# design.net
KiCad netlist of a schematic drawn in EasyEDA Pro
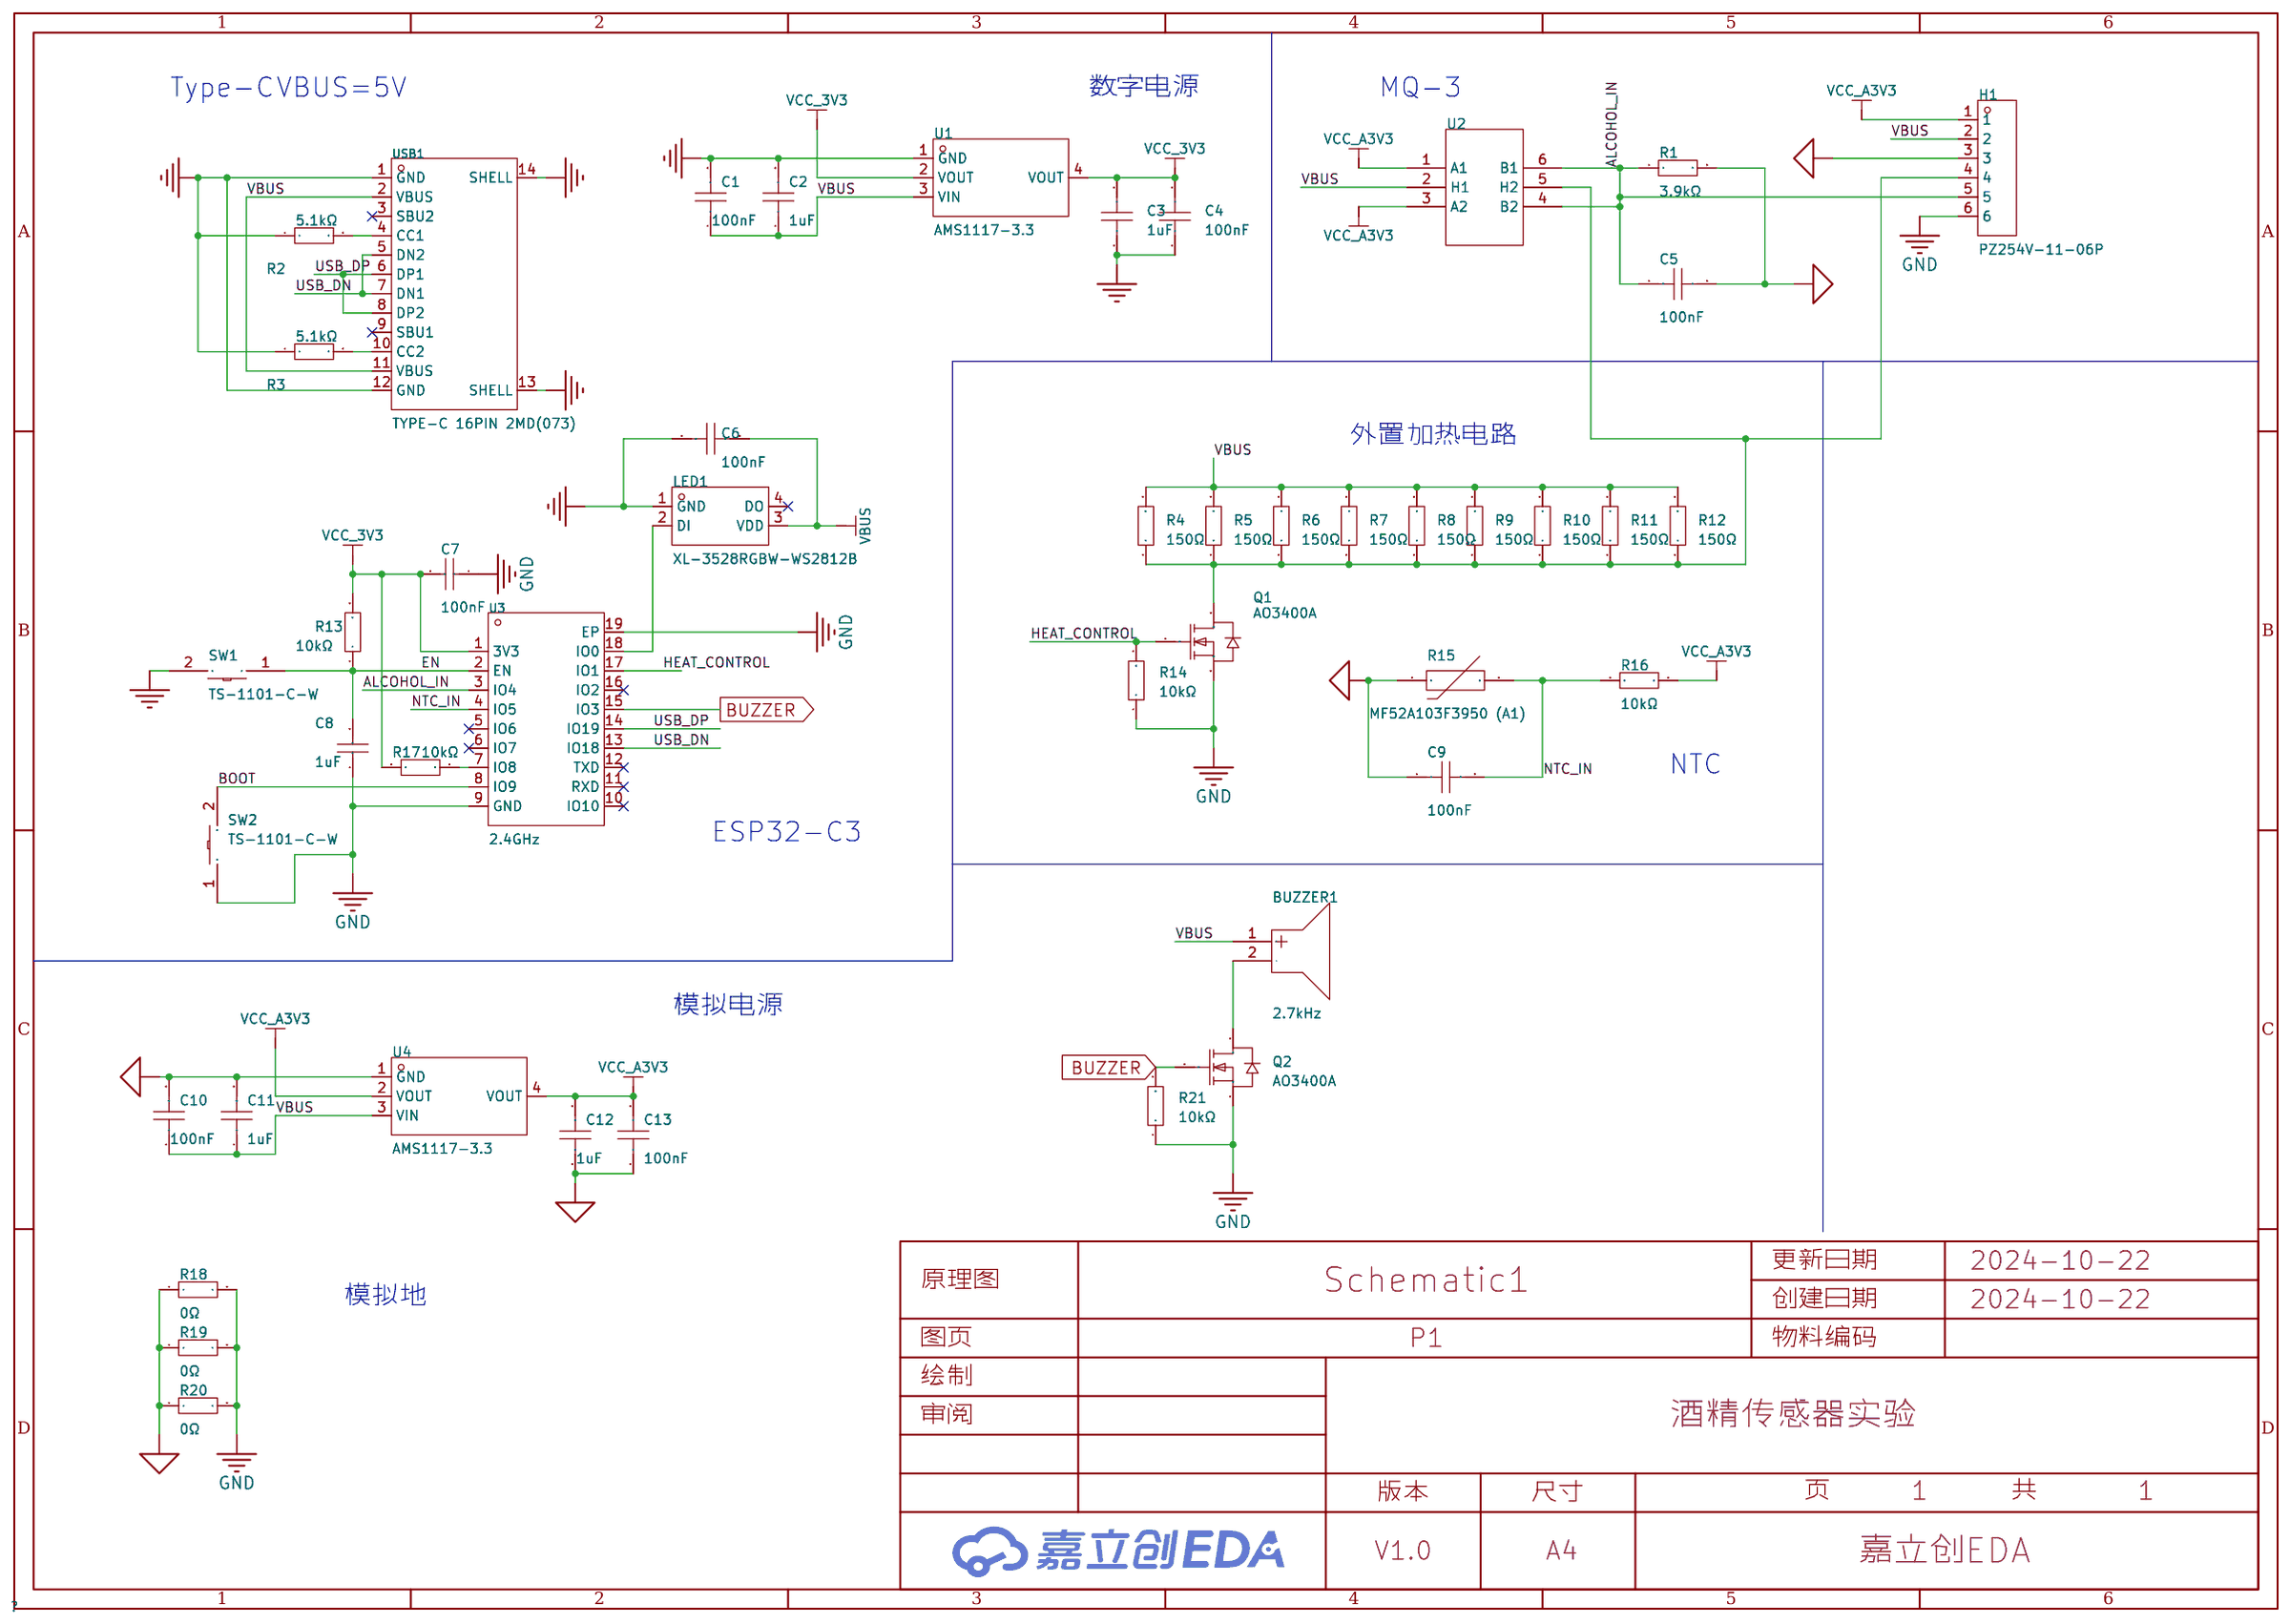
[diagram p0: schematic sheet]

(export (version "E")
  (design (tool "Eeschema 10.0.6"))
  (components
    (comp (ref "BUZZER1")
      (value "2.7kHz")
      (footprint "easyedapro:BUZ-SMD_L9.6-W9.6-LS10.0-R")
      (description "驱动方式:有源(内含驱动线路);频率:2.7kHz;声压(SPL):80dB@5V,10cm;")
      (fields
        (field (name "Manufacturer Part") "YS-SBZ9650DYB05")
        (field (name "Manufacturer") "Fengming(锋鸣电子)")
      )
      (libsource (lib "easyedapro") (part "YS-SBZ9650DYB05_C409830"))
    )
    (comp (ref "C1")
      (value "100nF")
      (footprint "easyedapro:C0603")
      (description "容值:100nF;精度:±10%;额定电压:50V;材质(温度系数):X7R;")
      (fields
        (field (name "Manufacturer Part") "CC0603KRX7R9BB104")
        (field (name "Manufacturer") "YAGEO(国巨)")
      )
      (libsource (lib "easyedapro") (part "CC0603KRX7R9BB104"))
    )
    (comp (ref "C2")
      (value "1uF")
      (footprint "easyedapro:C0603")
      (description "容值:1uF;精度:±10%;额定电压:50V;材质(温度系数):X5R;")
      (fields
        (field (name "Manufacturer Part") "CL10A105KB8NNNC")
        (field (name "Manufacturer") "SAMSUNG(三星)")
      )
      (libsource (lib "easyedapro") (part "CL10A105KB8NNNC"))
    )
    (comp (ref "C3")
      (value "1uF")
      (footprint "easyedapro:C0603")
      (description "容值:1uF;精度:±10%;额定电压:50V;材质(温度系数):X5R;")
      (fields
        (field (name "Manufacturer Part") "CL10A105KB8NNNC")
        (field (name "Manufacturer") "SAMSUNG(三星)")
      )
      (libsource (lib "easyedapro") (part "CL10A105KB8NNNC"))
    )
    (comp (ref "C4")
      (value "100nF")
      (footprint "easyedapro:C0603")
      (description "容值:100nF;精度:±10%;额定电压:50V;材质(温度系数):X7R;")
      (fields
        (field (name "Manufacturer Part") "CC0603KRX7R9BB104")
        (field (name "Manufacturer") "YAGEO(国巨)")
      )
      (libsource (lib "easyedapro") (part "CC0603KRX7R9BB104"))
    )
    (comp (ref "C5")
      (value "100nF")
      (footprint "easyedapro:C0603")
      (description "容值:100nF;精度:±10%;额定电压:50V;材质(温度系数):X7R;")
      (fields
        (field (name "Manufacturer Part") "CGA0603X7R104K500JT")
        (field (name "Manufacturer") "HRE(芯声)")
      )
      (libsource (lib "easyedapro") (part "cga0603x7r104k500jt"))
    )
    (comp (ref "C6")
      (value "100nF")
      (footprint "easyedapro:C0603")
      (description "容值:100nF;精度:±10%;额定电压:50V;材质(温度系数):X7R;")
      (fields
        (field (name "Manufacturer Part") "CC0603KRX7R9BB104")
        (field (name "Manufacturer") "YAGEO(国巨)")
      )
      (libsource (lib "easyedapro") (part "CC0603KRX7R9BB104"))
    )
    (comp (ref "C7")
      (value "100nF")
      (footprint "easyedapro:C0603")
      (description "容值:1uF;精度:±10%;额定电压:25V;温度系数:X5R;")
      (fields
        (field (name "Manufacturer Part") "CC0603KRX7R9BB104")
        (field (name "Manufacturer") "YAGEO(国巨)")
      )
      (libsource (lib "easyedapro") (part "CL10A105KA8NNNC"))
    )
    (comp (ref "C8")
      (value "1uF")
      (footprint "easyedapro:C0603")
      (description "容值:1uF;精度:±10%;额定电压:25V;温度系数:X5R;")
      (fields
        (field (name "Manufacturer Part") "CL10A105KA8NNNC")
        (field (name "Manufacturer") "SAMSUNG(三星)")
      )
      (libsource (lib "easyedapro") (part "CL10A105KA8NNNC"))
    )
    (comp (ref "C9")
      (value "100nF")
      (footprint "easyedapro:C0603")
      (description "容值:100nF;精度:±10%;额定电压:50V;材质(温度系数):X7R;")
      (fields
        (field (name "Manufacturer Part") "CGA0603X7R104K500JT")
        (field (name "Manufacturer") "HRE(芯声)")
      )
      (libsource (lib "easyedapro") (part "cga0603x7r104k500jt"))
    )
    (comp (ref "C10")
      (value "100nF")
      (footprint "easyedapro:C0603")
      (description "容值:100nF;精度:±10%;额定电压:50V;材质(温度系数):X7R;")
      (fields
        (field (name "Manufacturer Part") "CC0603KRX7R9BB104")
        (field (name "Manufacturer") "YAGEO(国巨)")
      )
      (libsource (lib "easyedapro") (part "CC0603KRX7R9BB104"))
    )
    (comp (ref "C11")
      (value "1uF")
      (footprint "easyedapro:C0603")
      (description "容值:1uF;精度:±10%;额定电压:50V;材质(温度系数):X5R;")
      (fields
        (field (name "Manufacturer Part") "CL10A105KB8NNNC")
        (field (name "Manufacturer") "SAMSUNG(三星)")
      )
      (libsource (lib "easyedapro") (part "CL10A105KB8NNNC"))
    )
    (comp (ref "C12")
      (value "1uF")
      (footprint "easyedapro:C0603")
      (description "容值:1uF;精度:±10%;额定电压:50V;材质(温度系数):X5R;")
      (fields
        (field (name "Manufacturer Part") "CL10A105KB8NNNC")
        (field (name "Manufacturer") "SAMSUNG(三星)")
      )
      (libsource (lib "easyedapro") (part "CL10A105KB8NNNC"))
    )
    (comp (ref "C13")
      (value "100nF")
      (footprint "easyedapro:C0603")
      (description "容值:100nF;精度:±10%;额定电压:50V;材质(温度系数):X7R;")
      (fields
        (field (name "Manufacturer Part") "CC0603KRX7R9BB104")
        (field (name "Manufacturer") "YAGEO(国巨)")
      )
      (libsource (lib "easyedapro") (part "CC0603KRX7R9BB104"))
    )
    (comp (ref "H1")
      (value "PZ254V-11-06P")
      (footprint "easyedapro:HDR-TH_6P-P2.54-V-M")
      (fields (field (name "Manufacturer") "XFCN(兴飞)"))
      (libsource (lib "easyedapro") (part "PZ254V-11-06P"))
    )
    (comp (ref "LED1")
      (value "XL-3528RGBW-WS2812B")
      (footprint "easyedapro:LED-SMD_4P-L3.5-W2.8-BR-1")
      (description "3528 七彩幻彩雾状 ws2812B 内置驱动IC")
      (fields (field (name "Manufacturer") "XINGLIGHT(成兴光)"))
      (libsource (lib "easyedapro") (part "XL-3528RGBW-WS2812B"))
    )
    (comp (ref "Q1")
      (value "AO3400A")
      (footprint "easyedapro:SOT-23-3_L2.9-W1.3-P1.90-LS2.4-BR")
      (fields (field (name "Manufacturer") "AOS"))
      (libsource (lib "easyedapro") (part "AO3400A"))
    )
    (comp (ref "Q2")
      (value "AO3400A")
      (footprint "easyedapro:SOT-23-3_L2.9-W1.3-P1.90-LS2.4-BR")
      (fields (field (name "Manufacturer") "AOS"))
      (libsource (lib "easyedapro") (part "AO3400A"))
    )
    (comp (ref "R1")
      (value "3.9kΩ")
      (footprint "easyedapro:R0603")
      (description "电阻类型:厚膜电阻;阻值:3.9kΩ;精度:±1%;功率:100mW;最大工作电压:75V;温度系数:±100ppm/°C;")
      (fields
        (field (name "Manufacturer Part") "0603WAF3901T5E")
        (field (name "Manufacturer") "UNI-ROYAL(厚声)")
      )
      (libsource (lib "easyedapro") (part "0603WAF3901T5E"))
    )
    (comp (ref "R2")
      (value "5.1kΩ")
      (fields
        (field (name "Manufacturer Part") "0603WAF5101T5E")
        (field (name "Manufacturer") "UNI-ROYAL(厚声)")
      )
      (libsource (lib "easyedapro") (part "电阻"))
    )
    (comp (ref "R3")
      (value "5.1kΩ")
      (fields
        (field (name "Manufacturer Part") "0603WAF5101T5E")
        (field (name "Manufacturer") "UNI-ROYAL(厚声)")
      )
      (libsource (lib "easyedapro") (part "电阻"))
    )
    (comp (ref "R4")
      (value "150Ω")
      (footprint "easyedapro:R0603")
      (description "电阻类型:厚膜电阻;阻值:150Ω;精度:±1%;功率:100mW;温度系数:±100ppm/°C;")
      (fields
        (field (name "Manufacturer Part") "0603WAF1500T5E")
        (field (name "Manufacturer") "UNI-ROYAL(厚声)")
      )
      (libsource (lib "easyedapro") (part "0603WAF1500T5E"))
    )
    (comp (ref "R5")
      (value "150Ω")
      (footprint "easyedapro:R0603")
      (description "电阻类型:厚膜电阻;阻值:150Ω;精度:±1%;功率:100mW;温度系数:±100ppm/°C;")
      (fields
        (field (name "Manufacturer Part") "0603WAF1500T5E")
        (field (name "Manufacturer") "UNI-ROYAL(厚声)")
      )
      (libsource (lib "easyedapro") (part "0603WAF1500T5E"))
    )
    (comp (ref "R6")
      (value "150Ω")
      (footprint "easyedapro:R0603")
      (description "电阻类型:厚膜电阻;阻值:150Ω;精度:±1%;功率:100mW;温度系数:±100ppm/°C;")
      (fields
        (field (name "Manufacturer Part") "0603WAF1500T5E")
        (field (name "Manufacturer") "UNI-ROYAL(厚声)")
      )
      (libsource (lib "easyedapro") (part "0603WAF1500T5E"))
    )
    (comp (ref "R7")
      (value "150Ω")
      (footprint "easyedapro:R0603")
      (description "电阻类型:厚膜电阻;阻值:150Ω;精度:±1%;功率:100mW;温度系数:±100ppm/°C;")
      (fields
        (field (name "Manufacturer Part") "0603WAF1500T5E")
        (field (name "Manufacturer") "UNI-ROYAL(厚声)")
      )
      (libsource (lib "easyedapro") (part "0603WAF1500T5E"))
    )
    (comp (ref "R8")
      (value "150Ω")
      (footprint "easyedapro:R0603")
      (description "电阻类型:厚膜电阻;阻值:150Ω;精度:±1%;功率:100mW;温度系数:±100ppm/°C;")
      (fields
        (field (name "Manufacturer Part") "0603WAF1500T5E")
        (field (name "Manufacturer") "UNI-ROYAL(厚声)")
      )
      (libsource (lib "easyedapro") (part "0603WAF1500T5E"))
    )
    (comp (ref "R9")
      (value "150Ω")
      (footprint "easyedapro:R0603")
      (description "电阻类型:厚膜电阻;阻值:150Ω;精度:±1%;功率:100mW;温度系数:±100ppm/°C;")
      (fields
        (field (name "Manufacturer Part") "0603WAF1500T5E")
        (field (name "Manufacturer") "UNI-ROYAL(厚声)")
      )
      (libsource (lib "easyedapro") (part "0603WAF1500T5E"))
    )
    (comp (ref "R10")
      (value "150Ω")
      (footprint "easyedapro:R0603")
      (description "电阻类型:厚膜电阻;阻值:150Ω;精度:±1%;功率:100mW;温度系数:±100ppm/°C;")
      (fields
        (field (name "Manufacturer Part") "0603WAF1500T5E")
        (field (name "Manufacturer") "UNI-ROYAL(厚声)")
      )
      (libsource (lib "easyedapro") (part "0603WAF1500T5E"))
    )
    (comp (ref "R11")
      (value "150Ω")
      (footprint "easyedapro:R0603")
      (description "电阻类型:厚膜电阻;阻值:150Ω;精度:±1%;功率:100mW;温度系数:±100ppm/°C;")
      (fields
        (field (name "Manufacturer Part") "0603WAF1500T5E")
        (field (name "Manufacturer") "UNI-ROYAL(厚声)")
      )
      (libsource (lib "easyedapro") (part "0603WAF1500T5E"))
    )
    (comp (ref "R12")
      (value "150Ω")
      (footprint "easyedapro:R0603")
      (description "电阻类型:厚膜电阻;阻值:150Ω;精度:±1%;功率:100mW;温度系数:±100ppm/°C;")
      (fields
        (field (name "Manufacturer Part") "0603WAF1500T5E")
        (field (name "Manufacturer") "UNI-ROYAL(厚声)")
      )
      (libsource (lib "easyedapro") (part "0603WAF1500T5E"))
    )
    (comp (ref "R13")
      (value "10kΩ")
      (fields
        (field (name "Manufacturer Part") "0603WAF1002T5E")
        (field (name "Manufacturer") "UNI-ROYAL(厚声)")
      )
      (libsource (lib "easyedapro") (part "电阻"))
    )
    (comp (ref "R14")
      (value "10kΩ")
      (fields
        (field (name "Manufacturer Part") "0603WAF1002T5E")
        (field (name "Manufacturer") "UNI-ROYAL(厚声)")
      )
      (libsource (lib "easyedapro") (part "电阻"))
    )
    (comp (ref "R15")
      (value "MF52A103F3950 (A1)")
      (footprint "easyedapro:RES-TH_L2.5-W2.5-P1.70-D0.3")
      (description "阻值(25°C):10kΩ;B值(25°C/50°C):3950K;电阻精度:±1%;功率:50mW;B值精度:±1%;最大稳态电流(25°C):-;")
      (fields (field (name "Manufacturer") "时恒"))
      (libsource (lib "easyedapro") (part "MF52A1103F3950(P334-4)"))
    )
    (comp (ref "R16")
      (value "10kΩ")
      (footprint "easyedapro:R0603")
      (description "电阻类型:厚膜电阻;阻值:10kΩ;精度:±1%;功率:100mW;")
      (fields
        (field (name "Manufacturer Part") "0603WAF1002T5E")
        (field (name "Manufacturer") "UNI-ROYAL(厚声)")
      )
      (libsource (lib "easyedapro") (part "0603WAF1002T5E"))
    )
    (comp (ref "R17")
      (value "10kΩ")
      (fields
        (field (name "Manufacturer Part") "0603WAF1002T5E")
        (field (name "Manufacturer") "UNI-ROYAL(厚声)")
      )
      (libsource (lib "easyedapro") (part "电阻"))
    )
    (comp (ref "R18")
      (value "0Ω")
      (footprint "easyedapro:R0603")
      (description "电阻类型:厚膜电阻;阻值:0Ω;精度:±1%;功率:100mW;最大工作电压:75V;")
      (fields
        (field (name "Manufacturer Part") "0603WAF0000T5E")
        (field (name "Manufacturer") "UNI-ROYAL(厚声)")
      )
      (libsource (lib "easyedapro") (part "0603WAF0000T5E"))
    )
    (comp (ref "R19")
      (value "0Ω")
      (footprint "easyedapro:R0603")
      (description "电阻类型:厚膜电阻;阻值:0Ω;精度:±1%;功率:100mW;最大工作电压:75V;")
      (fields
        (field (name "Manufacturer Part") "0603WAF0000T5E")
        (field (name "Manufacturer") "UNI-ROYAL(厚声)")
      )
      (libsource (lib "easyedapro") (part "0603WAF0000T5E"))
    )
    (comp (ref "R20")
      (value "0Ω")
      (footprint "easyedapro:R0603")
      (description "电阻类型:厚膜电阻;阻值:0Ω;精度:±1%;功率:100mW;最大工作电压:75V;")
      (fields
        (field (name "Manufacturer Part") "0603WAF0000T5E")
        (field (name "Manufacturer") "UNI-ROYAL(厚声)")
      )
      (libsource (lib "easyedapro") (part "0603WAF0000T5E"))
    )
    (comp (ref "R21")
      (value "10kΩ")
      (fields
        (field (name "Manufacturer Part") "0603WAF1002T5E")
        (field (name "Manufacturer") "UNI-ROYAL(厚声)")
      )
      (libsource (lib "easyedapro") (part "电阻"))
    )
    (comp (ref "SW1")
      (value "TS-1101-C-W")
      (footprint "easyedapro:SW-SMD_L6.0-W3.3-LS8.0")
      (description "触点电流:50mA;额定电压(AC):-;额定电压(DC):12V;额定功率:-;绝缘电阻:-;电路结构:单刀单掷;安装方式:立贴;带灯:无;作用力:260gf;机械寿命:5万次;带支架:否;")
      (fields (field (name "Manufacturer") "XKB Connectivity(中国星坤)"))
      (libsource (lib "easyedapro") (part "TS-1101-C-W"))
    )
    (comp (ref "SW2")
      (value "TS-1101-C-W")
      (footprint "easyedapro:SW-SMD_L6.0-W3.3-LS8.0")
      (description "触点电流:50mA;额定电压(AC):-;额定电压(DC):12V;额定功率:-;绝缘电阻:-;电路结构:单刀单掷;安装方式:立贴;带灯:无;作用力:260gf;机械寿命:5万次;带支架:否;")
      (fields (field (name "Manufacturer") "XKB Connectivity(中国星坤)"))
      (libsource (lib "easyedapro") (part "TS-1101-C-W"))
    )
    (comp (ref "U1")
      (value "AMS1117-3.3")
      (footprint "easyedapro:SOT-223-3_L6.5-W3.4-P2.30-LS7.0-BR")
      (description "输出类型:固定;最大输入电压:-;输出电压:3.3V;最大输出电流:1A;电源纹波抑制比(PSRR):72dB@(120Hz);输出极性:正极;")
      (fields (field (name "Manufacturer") "AMS"))
      (libsource (lib "easyedapro") (part "AMS1117-3.3"))
    )
    (comp (ref "U2")
      (value "~")
      (footprint "easyedapro:MQ-3-封装")
      (libsource (lib "easyedapro") (part "MQ-3"))
    )
    (comp (ref "U3")
      (value "2.4GHz")
      (footprint "easyedapro:BULETM-SMD_ESPRESSIF_ESP32-C3-WROOM-02-N4-4MB")
      (description "频率:2.4GHz;发射功率:20.5dBm;核心处理器:ESP32-C3;")
      (fields
        (field (name "Manufacturer Part") "ESP32-C3-WROOM-02-N4")
        (field (name "Manufacturer") "ESPRESSIF(乐鑫)")
      )
      (libsource (lib "easyedapro") (part "ESP32-C3-WROOM-02-N4(4MB)"))
    )
    (comp (ref "U4")
      (value "AMS1117-3.3")
      (footprint "easyedapro:SOT-223-3_L6.5-W3.4-P2.30-LS7.0-BR")
      (description "输出类型:固定;最大输入电压:-;输出电压:3.3V;最大输出电流:1A;电源纹波抑制比(PSRR):72dB@(120Hz);输出极性:正极;")
      (fields (field (name "Manufacturer") "AMS"))
      (libsource (lib "easyedapro") (part "AMS1117-3.3"))
    )
    (comp (ref "USB1")
      (value "TYPE-C 16PIN 2MD(073)")
      (footprint "easyedapro:USB-C-SMD_TYPE-C-6PIN-2MD-073")
      (description "连接器类型:Type-C;标准:-;公母:母座;触点数量:16;端口数量:1;安装方式:卧贴;额定电流 - 电源:5A;工作温度范围:-25℃~+85℃;")
      (fields (field (name "Manufacturer") "SHOU HAN(首韩)"))
      (libsource (lib "easyedapro") (part "TYPE-C 16PIN 2MD(073)"))
    )
  )
  (nets
    (net (code "1") (name "/ALCOHOL_IN") (class "Default")
      (node (ref "C5") (pin "1") (pinfunction "1_1") (pintype "unspecified"))
      (node (ref "H1") (pin "5") (pinfunction "5_5") (pintype "unspecified"))
      (node (ref "R1") (pin "1") (pinfunction "1_1") (pintype "input"))
      (node (ref "U2") (pin "4") (pinfunction "B2_4") (pintype "input"))
      (node (ref "U2") (pin "6") (pinfunction "B1_6") (pintype "input"))
      (node (ref "U3") (pin "3") (pinfunction "IO4_3") (pintype "input"))
    )
    (net (code "2") (name "/BOOT") (class "Default")
      (node (ref "SW2") (pin "2") (pinfunction "2_2") (pintype "input"))
      (node (ref "U3") (pin "8") (pinfunction "IO9_8") (pintype "input"))
    )
    (net (code "3") (name "/EN") (class "Default")
      (node (ref "C8") (pin "2") (pinfunction "2_2") (pintype "input"))
      (node (ref "R13") (pin "1") (pinfunction "1_1") (pintype "input"))
      (node (ref "SW1") (pin "1") (pinfunction "1_1") (pintype "input"))
      (node (ref "U3") (pin "2") (pinfunction "EN_2") (pintype "input"))
    )
    (net (code "4") (name "/HEAT_CONTROL") (class "Default")
      (node (ref "Q1") (pin "1") (pinfunction "G_1") (pintype "unspecified"))
      (node (ref "R14") (pin "2") (pinfunction "2_2") (pintype "input"))
      (node (ref "U3") (pin "17") (pinfunction "IO1_17") (pintype "input"))
    )
    (net (code "5") (name "/NTC_IN") (class "Default")
      (node (ref "C9") (pin "2") (pinfunction "2_2") (pintype "unspecified"))
      (node (ref "R15") (pin "2") (pinfunction "2_2") (pintype "unspecified"))
      (node (ref "R16") (pin "1") (pinfunction "1_1") (pintype "input"))
      (node (ref "U3") (pin "4") (pinfunction "IO5_4") (pintype "input"))
    )
    (net (code "6") (name "/USB_DN") (class "Default")
      (node (ref "U3") (pin "13") (pinfunction "IO18_13") (pintype "input"))
      (node (ref "USB1") (pin "5") (pinfunction "DN2_5") (pintype "unspecified"))
      (node (ref "USB1") (pin "7") (pinfunction "DN1_7") (pintype "unspecified"))
    )
    (net (code "7") (name "/USB_DP") (class "Default")
      (node (ref "U3") (pin "14") (pinfunction "IO19_14") (pintype "input"))
      (node (ref "USB1") (pin "6") (pinfunction "DP1_6") (pintype "unspecified"))
      (node (ref "USB1") (pin "8") (pinfunction "DP2_8") (pintype "unspecified"))
    )
    (net (code "8") (name "AGND") (class "Default")
      (node (ref "C10") (pin "2") (pinfunction "2_2") (pintype "unspecified"))
      (node (ref "C11") (pin "2") (pinfunction "2_2") (pintype "unspecified"))
      (node (ref "C12") (pin "1") (pinfunction "1_1") (pintype "unspecified"))
      (node (ref "C13") (pin "1") (pinfunction "1_1") (pintype "unspecified"))
      (node (ref "C5") (pin "2") (pinfunction "2_2") (pintype "unspecified"))
      (node (ref "C9") (pin "1") (pinfunction "1_1") (pintype "unspecified"))
      (node (ref "H1") (pin "3") (pinfunction "3_3") (pintype "unspecified"))
      (node (ref "R1") (pin "2") (pinfunction "2_2") (pintype "input"))
      (node (ref "R15") (pin "1") (pinfunction "1_1") (pintype "unspecified"))
      (node (ref "R18") (pin "1") (pinfunction "1_1") (pintype "input"))
      (node (ref "R19") (pin "1") (pinfunction "1_1") (pintype "input"))
      (node (ref "R20") (pin "1") (pinfunction "1_1") (pintype "input"))
      (node (ref "U4") (pin "1") (pinfunction "GND_1") (pintype "unspecified"))
    )
    (net (code "9") (name "BUZZER") (class "Default")
      (node (ref "Q2") (pin "1") (pinfunction "G_1") (pintype "unspecified"))
      (node (ref "R21") (pin "2") (pinfunction "2_2") (pintype "input"))
      (node (ref "U3") (pin "15") (pinfunction "IO3_15") (pintype "input"))
    )
    (net (code "10") (name "GND") (class "Default")
      (node (ref "C1") (pin "2") (pinfunction "2_2") (pintype "unspecified"))
      (node (ref "C2") (pin "2") (pinfunction "2_2") (pintype "unspecified"))
      (node (ref "C3") (pin "1") (pinfunction "1_1") (pintype "unspecified"))
      (node (ref "C4") (pin "1") (pinfunction "1_1") (pintype "unspecified"))
      (node (ref "C6") (pin "2") (pinfunction "2_2") (pintype "unspecified"))
      (node (ref "C7") (pin "1") (pinfunction "1_1") (pintype "input"))
      (node (ref "C8") (pin "1") (pinfunction "1_1") (pintype "input"))
      (node (ref "H1") (pin "6") (pinfunction "6_6") (pintype "unspecified"))
      (node (ref "LED1") (pin "1") (pinfunction "GND_1") (pintype "unspecified"))
      (node (ref "Q1") (pin "2") (pinfunction "S_2") (pintype "unspecified"))
      (node (ref "Q2") (pin "2") (pinfunction "S_2") (pintype "unspecified"))
      (node (ref "R14") (pin "1") (pinfunction "1_1") (pintype "input"))
      (node (ref "R18") (pin "2") (pinfunction "2_2") (pintype "input"))
      (node (ref "R19") (pin "2") (pinfunction "2_2") (pintype "input"))
      (node (ref "R2") (pin "1") (pinfunction "1_1") (pintype "input"))
      (node (ref "R20") (pin "2") (pinfunction "2_2") (pintype "input"))
      (node (ref "R21") (pin "1") (pinfunction "1_1") (pintype "input"))
      (node (ref "R3") (pin "1") (pinfunction "1_1") (pintype "input"))
      (node (ref "SW1") (pin "2") (pinfunction "2_2") (pintype "input"))
      (node (ref "SW2") (pin "1") (pinfunction "1_1") (pintype "input"))
      (node (ref "U1") (pin "1") (pinfunction "GND_1") (pintype "unspecified"))
      (node (ref "U3") (pin "19") (pinfunction "EP_19") (pintype "input"))
      (node (ref "U3") (pin "9") (pinfunction "GND_9") (pintype "input"))
      (node (ref "USB1") (pin "1") (pinfunction "GND_1") (pintype "unspecified"))
      (node (ref "USB1") (pin "12") (pinfunction "GND_12") (pintype "unspecified"))
      (node (ref "USB1") (pin "13") (pinfunction "SHELL_13") (pintype "unspecified"))
      (node (ref "USB1") (pin "14") (pinfunction "SHELL_14") (pintype "unspecified"))
    )
    (net (code "11") (name "Net-(BUZZER1--)") (class "Default")
      (node (ref "BUZZER1") (pin "2") (pinfunction "-_2") (pintype "unspecified"))
      (node (ref "Q2") (pin "3") (pinfunction "D_3") (pintype "unspecified"))
    )
    (net (code "12") (name "Net-(LED1-DI)") (class "Default")
      (node (ref "LED1") (pin "2") (pinfunction "DI_2") (pintype "unspecified"))
      (node (ref "U3") (pin "18") (pinfunction "IO0_18") (pintype "input"))
    )
    (net (code "13") (name "Net-(Q1-D)") (class "Default")
      (node (ref "H1") (pin "4") (pinfunction "4_4") (pintype "unspecified"))
      (node (ref "Q1") (pin "3") (pinfunction "D_3") (pintype "unspecified"))
      (node (ref "R10") (pin "1") (pinfunction "1_1") (pintype "input"))
      (node (ref "R11") (pin "1") (pinfunction "1_1") (pintype "input"))
      (node (ref "R12") (pin "1") (pinfunction "1_1") (pintype "input"))
      (node (ref "R4") (pin "1") (pinfunction "1_1") (pintype "input"))
      (node (ref "R5") (pin "1") (pinfunction "1_1") (pintype "input"))
      (node (ref "R6") (pin "1") (pinfunction "1_1") (pintype "input"))
      (node (ref "R7") (pin "1") (pinfunction "1_1") (pintype "input"))
      (node (ref "R8") (pin "1") (pinfunction "1_1") (pintype "input"))
      (node (ref "R9") (pin "1") (pinfunction "1_1") (pintype "input"))
      (node (ref "U2") (pin "5") (pinfunction "H2_5") (pintype "input"))
    )
    (net (code "14") (name "Net-(U3-IO8)") (class "Default")
      (node (ref "R17") (pin "1") (pinfunction "1_1") (pintype "input"))
      (node (ref "U3") (pin "7") (pinfunction "IO8_7") (pintype "input"))
    )
    (net (code "15") (name "Net-(USB1-CC1)") (class "Default")
      (node (ref "R2") (pin "2") (pinfunction "2_2") (pintype "input"))
      (node (ref "USB1") (pin "4") (pinfunction "CC1_4") (pintype "unspecified"))
    )
    (net (code "16") (name "Net-(USB1-CC2)") (class "Default")
      (node (ref "R3") (pin "2") (pinfunction "2_2") (pintype "input"))
      (node (ref "USB1") (pin "10") (pinfunction "CC2_10") (pintype "unspecified"))
    )
    (net (code "17") (name "VBUS") (class "Default")
      (node (ref "BUZZER1") (pin "1") (pinfunction "+_1") (pintype "unspecified"))
      (node (ref "C1") (pin "1") (pinfunction "1_1") (pintype "unspecified"))
      (node (ref "C10") (pin "1") (pinfunction "1_1") (pintype "unspecified"))
      (node (ref "C11") (pin "1") (pinfunction "1_1") (pintype "unspecified"))
      (node (ref "C2") (pin "1") (pinfunction "1_1") (pintype "unspecified"))
      (node (ref "C6") (pin "1") (pinfunction "1_1") (pintype "unspecified"))
      (node (ref "H1") (pin "2") (pinfunction "2_2") (pintype "unspecified"))
      (node (ref "LED1") (pin "3") (pinfunction "VDD_3") (pintype "unspecified"))
      (node (ref "R10") (pin "2") (pinfunction "2_2") (pintype "input"))
      (node (ref "R11") (pin "2") (pinfunction "2_2") (pintype "input"))
      (node (ref "R12") (pin "2") (pinfunction "2_2") (pintype "input"))
      (node (ref "R4") (pin "2") (pinfunction "2_2") (pintype "input"))
      (node (ref "R5") (pin "2") (pinfunction "2_2") (pintype "input"))
      (node (ref "R6") (pin "2") (pinfunction "2_2") (pintype "input"))
      (node (ref "R7") (pin "2") (pinfunction "2_2") (pintype "input"))
      (node (ref "R8") (pin "2") (pinfunction "2_2") (pintype "input"))
      (node (ref "R9") (pin "2") (pinfunction "2_2") (pintype "input"))
      (node (ref "U1") (pin "3") (pinfunction "VIN_3") (pintype "unspecified"))
      (node (ref "U2") (pin "2") (pinfunction "H1_2") (pintype "input"))
      (node (ref "U4") (pin "3") (pinfunction "VIN_3") (pintype "unspecified"))
      (node (ref "USB1") (pin "11") (pinfunction "VBUS_11") (pintype "unspecified"))
      (node (ref "USB1") (pin "2") (pinfunction "VBUS_2") (pintype "unspecified"))
    )
    (net (code "18") (name "VCC_3V3") (class "Default")
      (node (ref "C3") (pin "2") (pinfunction "2_2") (pintype "unspecified"))
      (node (ref "C4") (pin "2") (pinfunction "2_2") (pintype "unspecified"))
      (node (ref "C7") (pin "2") (pinfunction "2_2") (pintype "input"))
      (node (ref "R13") (pin "2") (pinfunction "2_2") (pintype "input"))
      (node (ref "R17") (pin "2") (pinfunction "2_2") (pintype "input"))
      (node (ref "U1") (pin "2") (pinfunction "VOUT_2") (pintype "unspecified"))
      (node (ref "U1") (pin "4") (pinfunction "VOUT_4") (pintype "unspecified"))
      (node (ref "U3") (pin "1") (pinfunction "3V3_1") (pintype "input"))
    )
    (net (code "19") (name "VCC_A3V3") (class "Default")
      (node (ref "C12") (pin "2") (pinfunction "2_2") (pintype "unspecified"))
      (node (ref "C13") (pin "2") (pinfunction "2_2") (pintype "unspecified"))
      (node (ref "H1") (pin "1") (pinfunction "1_1") (pintype "unspecified"))
      (node (ref "R16") (pin "2") (pinfunction "2_2") (pintype "input"))
      (node (ref "U2") (pin "1") (pinfunction "A1_1") (pintype "input"))
      (node (ref "U2") (pin "3") (pinfunction "A2_3") (pintype "input"))
      (node (ref "U4") (pin "2") (pinfunction "VOUT_2") (pintype "unspecified"))
      (node (ref "U4") (pin "4") (pinfunction "VOUT_4") (pintype "unspecified"))
    )
    (net (code "20") (name "unconnected-(LED1-DO-Pad4)") (class "Default")
      (node (ref "LED1") (pin "4") (pinfunction "DO_4") (pintype "unspecified+no_connect"))
    )
    (net (code "21") (name "unconnected-(U3-IO2-Pad16)") (class "Default")
      (node (ref "U3") (pin "16") (pinfunction "IO2_16") (pintype "input+no_connect"))
    )
    (net (code "22") (name "unconnected-(U3-IO6-Pad5)") (class "Default")
      (node (ref "U3") (pin "5") (pinfunction "IO6_5") (pintype "input+no_connect"))
    )
    (net (code "23") (name "unconnected-(U3-IO7-Pad6)") (class "Default")
      (node (ref "U3") (pin "6") (pinfunction "IO7_6") (pintype "input+no_connect"))
    )
    (net (code "24") (name "unconnected-(U3-IO10-Pad10)") (class "Default")
      (node (ref "U3") (pin "10") (pinfunction "IO10_10") (pintype "input+no_connect"))
    )
    (net (code "25") (name "unconnected-(U3-RXD-Pad11)") (class "Default")
      (node (ref "U3") (pin "11") (pinfunction "RXD_11") (pintype "input+no_connect"))
    )
    (net (code "26") (name "unconnected-(U3-TXD-Pad12)") (class "Default")
      (node (ref "U3") (pin "12") (pinfunction "TXD_12") (pintype "input+no_connect"))
    )
    (net (code "27") (name "unconnected-(USB1-SBU1-Pad9)") (class "Default")
      (node (ref "USB1") (pin "9") (pinfunction "SBU1_9") (pintype "unspecified+no_connect"))
    )
    (net (code "28") (name "unconnected-(USB1-SBU2-Pad3)") (class "Default")
      (node (ref "USB1") (pin "3") (pinfunction "SBU2_3") (pintype "unspecified+no_connect"))
    )
  )
)
